# nxtcam_5.net
KiCad netlist of a schematic drawn in EAGLE
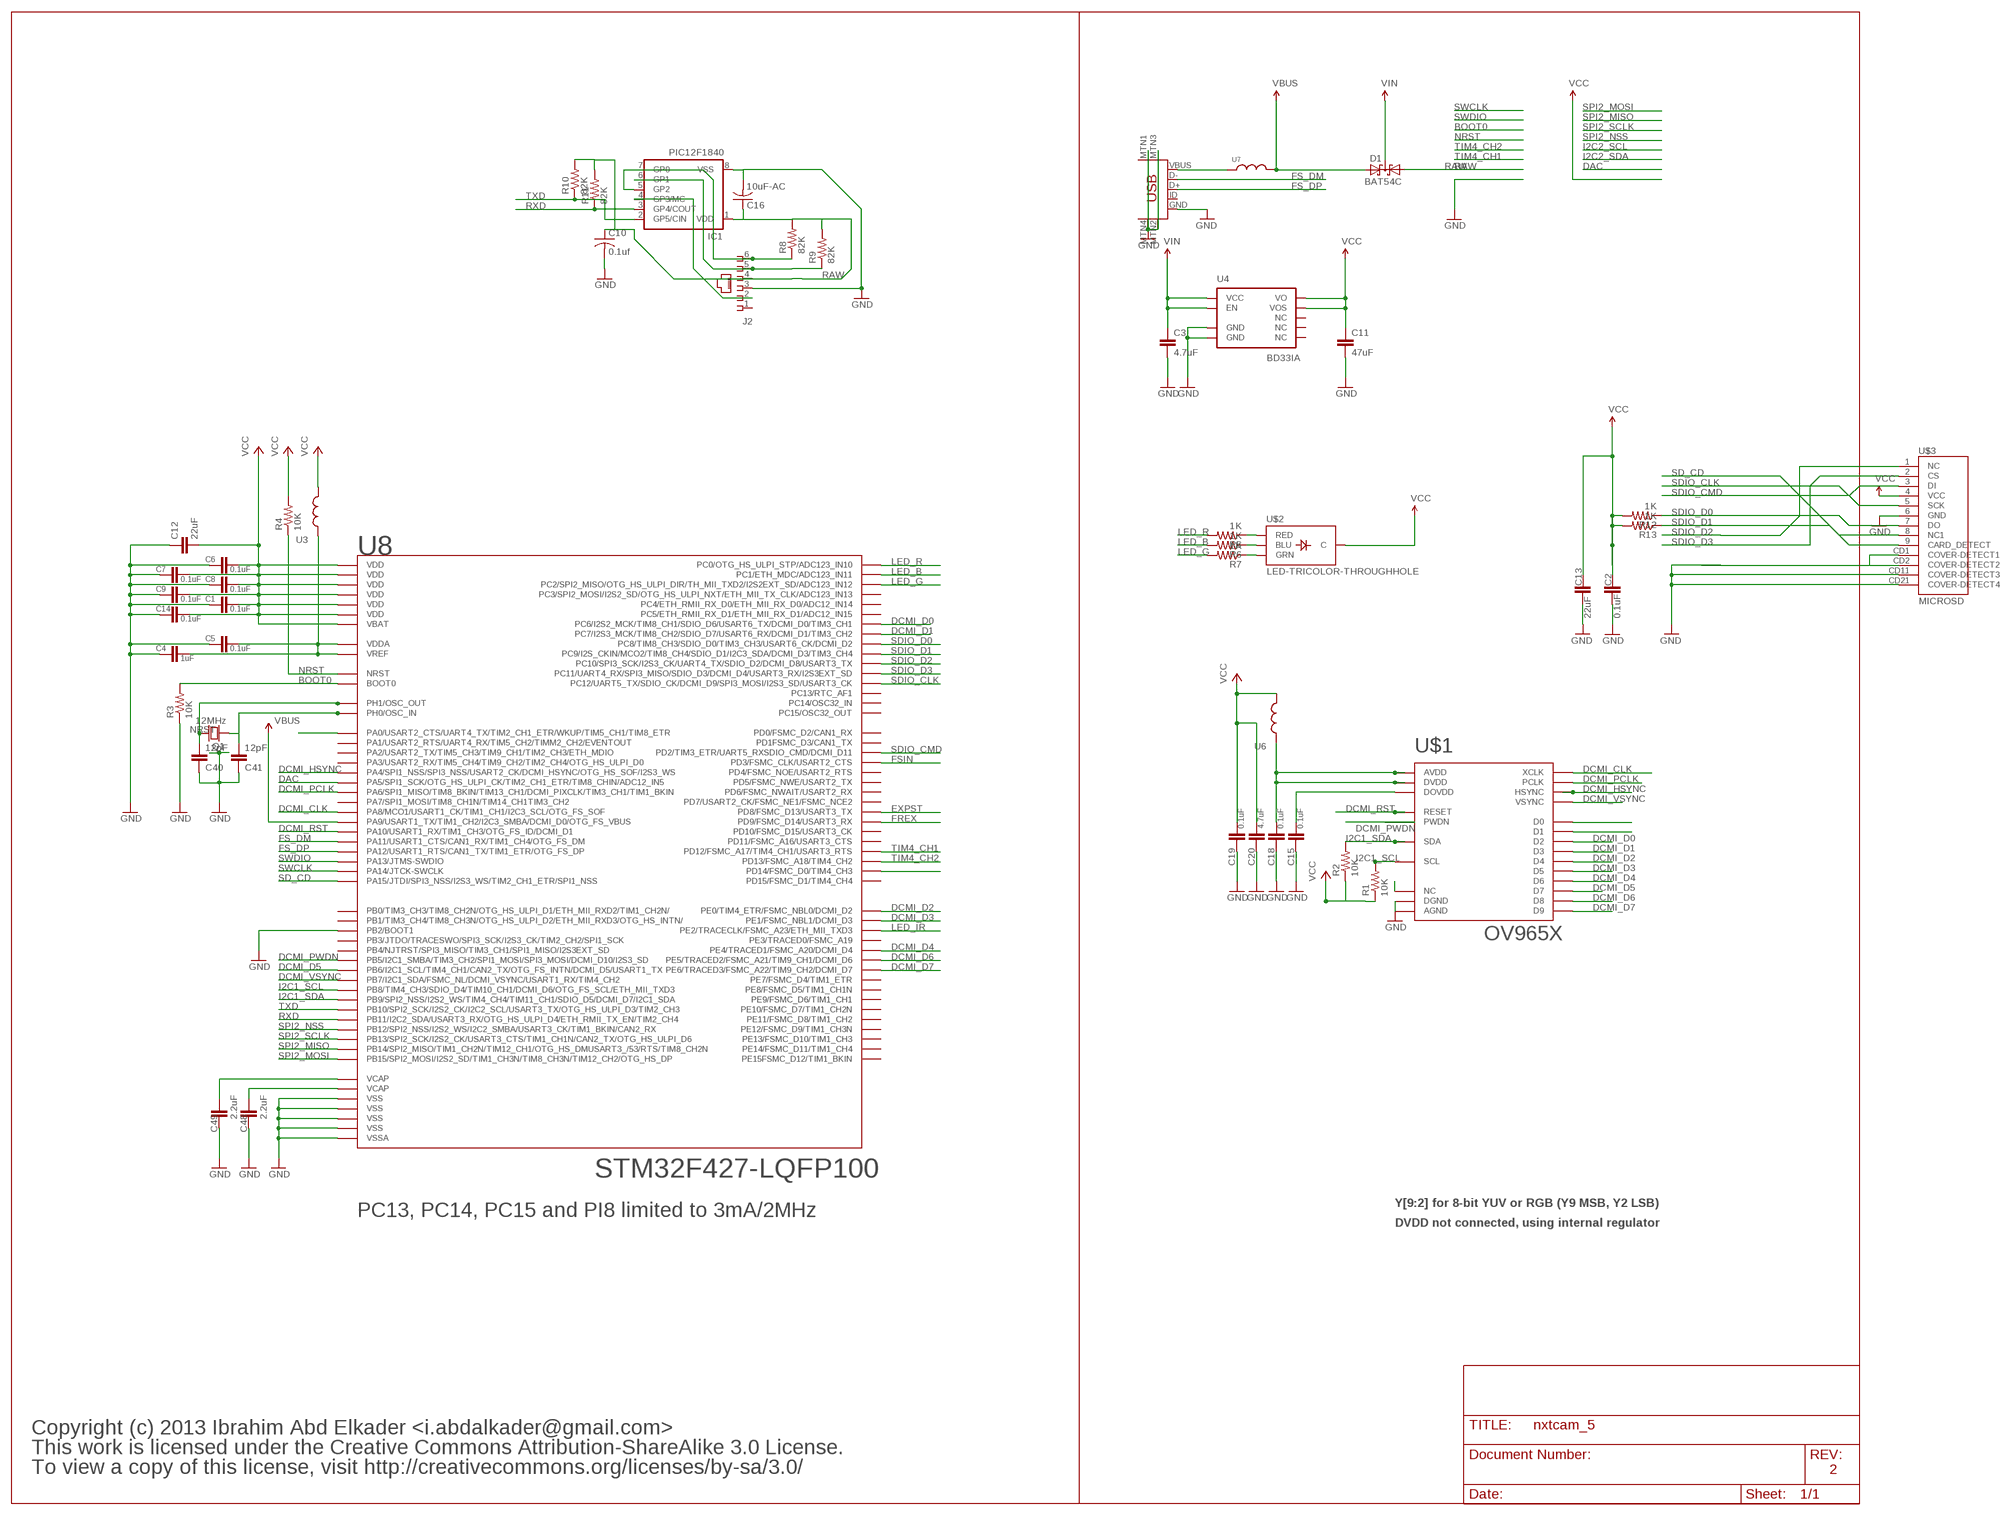
[diagram p0: schematic, sheet 1]

(export (version "E")
  (design (tool "Eeschema 10.0.6"))
  (components
    (comp (ref "C1")
      (value "0.1uF")
      (footprint "eagle-import:0603-CAP")
      (libsource (lib "eagle-import") (part "CAP0603-CAP"))
    )
    (comp (ref "C2")
      (value "0.1uF")
      (footprint "eagle-import:0603-CAP")
      (libsource (lib "eagle-import") (part "CAP0603-CAP"))
    )
    (comp (ref "C3")
      (value "4.7uF")
      (footprint "eagle-import:0603-CAP")
      (libsource (lib "eagle-import") (part "CAP0603-CAP"))
    )
    (comp (ref "C4")
      (value "1uF")
      (footprint "eagle-import:0603-CAP")
      (libsource (lib "eagle-import") (part "CAP0603-CAP"))
    )
    (comp (ref "C5")
      (value "0.1uF")
      (footprint "eagle-import:0603-CAP")
      (libsource (lib "eagle-import") (part "CAP0603-CAP"))
    )
    (comp (ref "C6")
      (value "0.1uF")
      (footprint "eagle-import:0603-CAP")
      (libsource (lib "eagle-import") (part "CAP0603-CAP"))
    )
    (comp (ref "C7")
      (value "0.1uF")
      (footprint "eagle-import:0603-CAP")
      (libsource (lib "eagle-import") (part "CAP0603-CAP"))
    )
    (comp (ref "C8")
      (value "0.1uF")
      (footprint "eagle-import:0603-CAP")
      (libsource (lib "eagle-import") (part "CAP0603-CAP"))
    )
    (comp (ref "C9")
      (value "0.1uF")
      (footprint "eagle-import:0603-CAP")
      (libsource (lib "eagle-import") (part "CAP0603-CAP"))
    )
    (comp (ref "C10")
      (value "0.1uf")
      (footprint "eagle-import:C0603K")
      (libsource (lib "eagle-import") (part "wbyb_C-USC0603K"))
    )
    (comp (ref "C11")
      (value "47uF")
      (footprint "eagle-import:1206")
      (libsource (lib "eagle-import") (part "CAP1206"))
    )
    (comp (ref "C12")
      (value "22uF")
      (footprint "eagle-import:0805")
      (libsource (lib "eagle-import") (part "CAP0805"))
    )
    (comp (ref "C13")
      (value "22uF")
      (footprint "eagle-import:0805")
      (libsource (lib "eagle-import") (part "CAP0805"))
    )
    (comp (ref "C14")
      (value "0.1uF")
      (footprint "eagle-import:0603-CAP")
      (libsource (lib "eagle-import") (part "CAP0603-CAP"))
    )
    (comp (ref "C15")
      (value "0.1uF")
      (footprint "eagle-import:0603-CAP")
      (libsource (lib "eagle-import") (part "CAP0603-CAP"))
    )
    (comp (ref "C16")
      (value "10uF-AC")
      (footprint "eagle-import:C1206K")
      (libsource (lib "eagle-import") (part "C-USC1206K"))
    )
    (comp (ref "C18")
      (value "0.1uF")
      (footprint "eagle-import:0603-CAP")
      (libsource (lib "eagle-import") (part "CAP0603-CAP"))
    )
    (comp (ref "C19")
      (value "0.1uF")
      (footprint "eagle-import:0603-CAP")
      (libsource (lib "eagle-import") (part "CAP0603-CAP"))
    )
    (comp (ref "C20")
      (value "4.7uF")
      (footprint "eagle-import:0603-CAP")
      (libsource (lib "eagle-import") (part "CAP0603-CAP"))
    )
    (comp (ref "C40")
      (value "12pF")
      (footprint "eagle-import:0603-CAP")
      (libsource (lib "eagle-import") (part "CAP0603-CAP"))
    )
    (comp (ref "C41")
      (value "12pF")
      (footprint "eagle-import:0603-CAP")
      (libsource (lib "eagle-import") (part "CAP0603-CAP"))
    )
    (comp (ref "C48")
      (value "2.2uF")
      (footprint "eagle-import:0603-CAP")
      (libsource (lib "eagle-import") (part "CAP0603-CAP"))
    )
    (comp (ref "C49")
      (value "2.2uF")
      (footprint "eagle-import:0603-CAP")
      (libsource (lib "eagle-import") (part "CAP0603-CAP"))
    )
    (comp (ref "D1")
      (value "BAT54C")
      (footprint "eagle-import:SOT23")
      (libsource (lib "eagle-import") (part "BAT54C"))
    )
    (comp (ref "IC1")
      (value "PIC12F1840")
      (footprint "eagle-import:SOIC08")
      (libsource (lib "eagle-import") (part "PIC12F1840"))
    )
    (comp (ref "J2")
      (value "NXTCONN0")
      (footprint "eagle-import:NXTCONN0")
      (libsource (lib "eagle-import") (part "NXTCONN0"))
    )
    (comp (ref "Q1")
      (value "12MHz")
      (footprint "eagle-import:TXC-SMD-50X32")
      (libsource (lib "eagle-import") (part "TXC-CRYSTAL50X32"))
    )
    (comp (ref "R1")
      (value "10K")
      (footprint "eagle-import:0603-RES")
      (libsource (lib "eagle-import") (part "RESISTOR0603-RES"))
    )
    (comp (ref "R2")
      (value "10K")
      (footprint "eagle-import:0603-RES")
      (libsource (lib "eagle-import") (part "RESISTOR0603-RES"))
    )
    (comp (ref "R3")
      (value "10K")
      (footprint "eagle-import:0603-RES")
      (libsource (lib "eagle-import") (part "RESISTOR0603-RES"))
    )
    (comp (ref "R4")
      (value "10K")
      (footprint "eagle-import:0603-RES")
      (libsource (lib "eagle-import") (part "RESISTOR0603-RES"))
    )
    (comp (ref "R5")
      (value "1K")
      (footprint "eagle-import:0603-RES")
      (libsource (lib "eagle-import") (part "RESISTOR0603-RES"))
    )
    (comp (ref "R6")
      (value "1K")
      (footprint "eagle-import:0603-RES")
      (libsource (lib "eagle-import") (part "RESISTOR0603-RES"))
    )
    (comp (ref "R7")
      (value "1K")
      (footprint "eagle-import:0603-RES")
      (libsource (lib "eagle-import") (part "RESISTOR0603-RES"))
    )
    (comp (ref "R8")
      (value "82K")
      (footprint "eagle-import:R0603")
      (libsource (lib "eagle-import") (part "R-US_R0603"))
    )
    (comp (ref "R9")
      (value "82K")
      (footprint "eagle-import:R0603")
      (libsource (lib "eagle-import") (part "R-US_R0603"))
    )
    (comp (ref "R10")
      (value "82K")
      (footprint "eagle-import:R0603")
      (libsource (lib "eagle-import") (part "R-US_R0603"))
    )
    (comp (ref "R11")
      (value "82K")
      (footprint "eagle-import:R0603")
      (libsource (lib "eagle-import") (part "R-US_R0603"))
    )
    (comp (ref "R12")
      (value "1K")
      (footprint "eagle-import:0603-RES")
      (libsource (lib "eagle-import") (part "RESISTOR0603-RES"))
    )
    (comp (ref "R13")
      (value "1K")
      (footprint "eagle-import:0603-RES")
      (libsource (lib "eagle-import") (part "RESISTOR0603-RES"))
    )
    (comp (ref "U$1")
      (value "OV965X")
      (footprint "eagle-import:OV965X")
      (libsource (lib "eagle-import") (part "OV965X"))
    )
    (comp (ref "U$2")
      (value "LED-TRICOLOR-THROUGHHOLE")
      (footprint "eagle-import:LED_TRICOLOR_THROUGHHOLE_SM")
      (libsource (lib "eagle-import") (part "LED-TRICOLOR-THROUGHHOLE"))
    )
    (comp (ref "U$3")
      (value "MICROSD")
      (footprint "eagle-import:MICROSD_CN")
      (libsource (lib "eagle-import") (part "MICROSD"))
    )
    (comp (ref "U$4")
      (value "USB-MINIBTH")
      (footprint "eagle-import:USB-MINIB-ALIGNPINS")
      (libsource (lib "eagle-import") (part "USB-MINIBTH"))
    )
    (comp (ref "U3")
      (value "INDUCTOR0603")
      (footprint "eagle-import:0603")
      (libsource (lib "eagle-import") (part "INDUCTOR0603"))
    )
    (comp (ref "U4")
      (value "BD33IA")
      (footprint "eagle-import:HTSOP-J8")
      (libsource (lib "eagle-import") (part "BD33IA"))
    )
    (comp (ref "U6")
      (value "INDUCTOR0603")
      (footprint "eagle-import:0603")
      (libsource (lib "eagle-import") (part "INDUCTOR0603"))
    )
    (comp (ref "U7")
      (value "INDUCTOR0603")
      (footprint "eagle-import:0603")
      (libsource (lib "eagle-import") (part "INDUCTOR0603"))
    )
    (comp (ref "U8")
      (value "STM32F427-LQFP100")
      (footprint "eagle-import:LQFP100")
      (libsource (lib "eagle-import") (part "STM32F407LQFP100"))
    )
  )
  (nets
    (net (code "1") (name "/BOOT0") (class "Default")
      (node (ref "R3") (pin "2") (pinfunction "2_2") (pintype "passive"))
      (node (ref "U8") (pin "94") (pinfunction "BOOT0_94") (pintype "bidirectional"))
    )
    (net (code "2") (name "/DAC") (class "Default")
      (node (ref "U8") (pin "30") (pinfunction "PA5/SPI1_SCK/OTG_HS_ULPI_CK/TIM2_CH1_ETR/TIM8_CHIN/ADC12_IN5_30") (pintype "bidirectional"))
    )
    (net (code "3") (name "/DCMI_CLK") (class "Default")
      (node (ref "U$1") (pin "P$13") (pinfunction "XCLK_P$13") (pintype "bidirectional"))
      (node (ref "U8") (pin "67") (pinfunction "PA8/MCO1/USART1_CK/TIM1_CH1/I2C3_SCL/OTG_FS_SOF_67") (pintype "bidirectional"))
    )
    (net (code "4") (name "/DCMI_D0") (class "Default")
      (node (ref "U$1") (pin "P$19") (pinfunction "D2_P$19") (pintype "bidirectional"))
      (node (ref "U8") (pin "63") (pinfunction "PC6/I2S2_MCK/TIM8_CH1/SDIO_D6/USART6_TX/DCMI_D0/TIM3_CH1_63") (pintype "bidirectional"))
    )
    (net (code "5") (name "/DCMI_D1") (class "Default")
      (node (ref "U$1") (pin "P$21") (pinfunction "D3_P$21") (pintype "bidirectional"))
      (node (ref "U8") (pin "64") (pinfunction "PC7/I2S3_MCK/TIM8_CH2/SDIO_D7/USART6_RX/DCMI_D1/TIM3_CH2_64") (pintype "bidirectional"))
    )
    (net (code "6") (name "/DCMI_D2") (class "Default")
      (node (ref "U$1") (pin "P$22") (pinfunction "D4_P$22") (pintype "bidirectional"))
      (node (ref "U8") (pin "97") (pinfunction "PE0/TIM4_ETR/FSMC_NBL0/DCMI_D2_97") (pintype "bidirectional"))
    )
    (net (code "7") (name "/DCMI_D3") (class "Default")
      (node (ref "U$1") (pin "P$20") (pinfunction "D5_P$20") (pintype "bidirectional"))
      (node (ref "U8") (pin "98") (pinfunction "PE1/FSMC_NBL1/DCMI_D3_98") (pintype "bidirectional"))
    )
    (net (code "8") (name "/DCMI_D4") (class "Default")
      (node (ref "U$1") (pin "P$18") (pinfunction "D6_P$18") (pintype "bidirectional"))
      (node (ref "U8") (pin "3") (pinfunction "PE4/TRACED1/FSMC_A20/DCMI_D4_3") (pintype "bidirectional"))
    )
    (net (code "9") (name "/DCMI_D5") (class "Default")
      (node (ref "U$1") (pin "P$16") (pinfunction "D7_P$16") (pintype "bidirectional"))
      (node (ref "U8") (pin "92") (pinfunction "PB6/I2C1_SCL/TIM4_CH1/CAN2_TX/OTG_FS_INTN/DCMI_D5/USART1_TX_92") (pintype "bidirectional"))
    )
    (net (code "10") (name "/DCMI_D6") (class "Default")
      (node (ref "U$1") (pin "P$14") (pinfunction "D8_P$14") (pintype "bidirectional"))
      (node (ref "U8") (pin "4") (pinfunction "PE5/TRACED2/FSMC_A21/TIM9_CH1/DCMI_D6_4") (pintype "bidirectional"))
    )
    (net (code "11") (name "/DCMI_D7") (class "Default")
      (node (ref "U$1") (pin "P$12") (pinfunction "D9_P$12") (pintype "bidirectional"))
      (node (ref "U8") (pin "5") (pinfunction "PE6/TRACED3/FSMC_A22/TIM9_CH2/DCMI_D7_5") (pintype "bidirectional"))
    )
    (net (code "12") (name "/DCMI_HSYNC") (class "Default")
      (node (ref "U$1") (pin "P$9") (pinfunction "HSYNC_P$9") (pintype "bidirectional"))
      (node (ref "U8") (pin "29") (pinfunction "PA4/SPI1_NSS/SPI3_NSS/USART2_CK/DCMI_HSYNC/OTG_HS_SOF/I2S3_WS_29") (pintype "bidirectional"))
    )
    (net (code "13") (name "/DCMI_PCLK") (class "Default")
      (node (ref "U$1") (pin "P$17") (pinfunction "PCLK_P$17") (pintype "bidirectional"))
      (node (ref "U8") (pin "31") (pinfunction "PA6/SPI1_MISO/TIM8_BKIN/TIM13_CH1/DCMI_PIXCLK/TIM3_CH1/TIM1_BKIN_31") (pintype "bidirectional"))
    )
    (net (code "14") (name "/DCMI_PWDN") (class "Default")
      (node (ref "U$1") (pin "P$8") (pinfunction "PWDN_P$8") (pintype "bidirectional"))
      (node (ref "U8") (pin "91") (pinfunction "PB5/I2C1_SMBA/TIM3_CH2/SPI1_MOSI/SPI3_MOSI/DCMI_D10/I2S3_SD_91") (pintype "bidirectional"))
    )
    (net (code "15") (name "/DCMI_RST") (class "Default")
      (node (ref "U$1") (pin "P$6") (pinfunction "RESET_P$6") (pintype "bidirectional"))
      (node (ref "U8") (pin "69") (pinfunction "PA10/USART1_RX/TIM1_CH3/OTG_FS_ID/DCMI_D1_69") (pintype "bidirectional"))
    )
    (net (code "16") (name "/DCMI_VSYNC") (class "Default")
      (node (ref "U$1") (pin "P$7") (pinfunction "VSYNC_P$7") (pintype "bidirectional"))
      (node (ref "U8") (pin "93") (pinfunction "PB7/I2C1_SDA/FSMC_NL/DCMI_VSYNC/USART1_RX/TIM4_CH2_93") (pintype "bidirectional"))
    )
    (net (code "17") (name "/EXPST") (class "Default")
      (node (ref "U8") (pin "55") (pinfunction "PD8/FSMC_D13/USART3_TX_55") (pintype "bidirectional"))
    )
    (net (code "18") (name "/FREX") (class "Default")
      (node (ref "U8") (pin "56") (pinfunction "PD9/FSMC_D14/USART3_RX_56") (pintype "bidirectional"))
    )
    (net (code "19") (name "/FSIN") (class "Default")
      (node (ref "U8") (pin "84") (pinfunction "PD3/FSMC_CLK/USART2_CTS_84") (pintype "bidirectional"))
    )
    (net (code "20") (name "/FS_DM") (class "Default")
      (node (ref "U$4") (pin "D-") (pinfunction "D-_D-") (pintype "bidirectional"))
      (node (ref "U8") (pin "70") (pinfunction "PA11/USART1_CTS/CAN1_RX/TIM1_CH4/OTG_FS_DM_70") (pintype "bidirectional"))
    )
    (net (code "21") (name "/FS_DP") (class "Default")
      (node (ref "U$4") (pin "D+") (pinfunction "D+_D+") (pintype "bidirectional"))
      (node (ref "U8") (pin "71") (pinfunction "PA12/USART1_RTS/CAN1_TX/TIM1_ETR/OTG_FS_DP_71") (pintype "bidirectional"))
    )
    (net (code "22") (name "/I2C1_SCL") (class "Default")
      (node (ref "R1") (pin "2") (pinfunction "2_2") (pintype "passive"))
      (node (ref "U$1") (pin "P$5") (pinfunction "SCL_P$5") (pintype "bidirectional"))
      (node (ref "U8") (pin "95") (pinfunction "PB8/TIM4_CH3/SDIO_D4/TIM10_CH1/DCMI_D6/OTG_FS_SCL/ETH_MII_TXD3_95") (pintype "bidirectional"))
    )
    (net (code "23") (name "/I2C1_SDA") (class "Default")
      (node (ref "R2") (pin "2") (pinfunction "2_2") (pintype "passive"))
      (node (ref "U$1") (pin "P$3") (pinfunction "SDA_P$3") (pintype "bidirectional"))
      (node (ref "U8") (pin "96") (pinfunction "PB9/SPI2_NSS/I2S2_WS/TIM4_CH4/TIM11_CH1/SDIO_D5/DCMI_D7/I2C1_SDA_96") (pintype "bidirectional"))
    )
    (net (code "26") (name "/LED_B") (class "Default")
      (node (ref "R6") (pin "2") (pinfunction "2_2") (pintype "passive"))
      (node (ref "U8") (pin "16") (pinfunction "PC1/ETH_MDC/ADC123_IN11_16") (pintype "bidirectional"))
    )
    (net (code "27") (name "/LED_G") (class "Default")
      (node (ref "R7") (pin "2") (pinfunction "2_2") (pintype "passive"))
      (node (ref "U8") (pin "17") (pinfunction "PC2/SPI2_MISO/OTG_HS_ULPI_DIR/TH_MII_TXD2/I2S2EXT_SD/ADC123_IN12_17") (pintype "bidirectional"))
    )
    (net (code "28") (name "/LED_IR") (class "Default")
      (node (ref "U8") (pin "1") (pinfunction "PE2/TRACECLK/FSMC_A23/ETH_MII_TXD3_1") (pintype "bidirectional"))
    )
    (net (code "29") (name "/LED_R") (class "Default")
      (node (ref "R5") (pin "2") (pinfunction "2_2") (pintype "passive"))
      (node (ref "U8") (pin "15") (pinfunction "PC0/OTG_HS_ULPI_STP/ADC123_IN10_15") (pintype "bidirectional"))
    )
    (net (code "30") (name "/NRST") (class "Default")
      (node (ref "R4") (pin "1") (pinfunction "1_1") (pintype "passive"))
      (node (ref "U8") (pin "14") (pinfunction "NRST_14") (pintype "bidirectional"))
    )
    (net (code "31") (name "/RAW") (class "Default")
      (node (ref "C10") (pin "1") (pinfunction "1_1") (pintype "passive"))
      (node (ref "C16") (pin "1") (pinfunction "1_1") (pintype "passive"))
      (node (ref "D1") (pin "1") (pinfunction "A1_1") (pintype "passive"))
      (node (ref "IC1") (pin "1") (pinfunction "VDD_1") (pintype "power_in"))
      (node (ref "J2") (pin "4") (pinfunction "4_4") (pintype "passive"))
      (node (ref "R10") (pin "2") (pinfunction "2_2") (pintype "passive"))
      (node (ref "R11") (pin "2") (pinfunction "2_2") (pintype "passive"))
      (node (ref "R8") (pin "2") (pinfunction "2_2") (pintype "passive"))
      (node (ref "R9") (pin "2") (pinfunction "2_2") (pintype "passive"))
    )
    (net (code "32") (name "/RXD") (class "Default")
      (node (ref "IC1") (pin "3") (pinfunction "GP4/COUT_3") (pintype "bidirectional"))
      (node (ref "R11") (pin "1") (pinfunction "1_1") (pintype "passive"))
      (node (ref "U8") (pin "48") (pinfunction "PB11/I2C2_SDA/USART3_RX/OTG_HS_ULPI_D4/ETH_RMII_TX_EN/TIM2_CH4_48") (pintype "bidirectional"))
    )
    (net (code "33") (name "/SDIO_CLK") (class "Default")
      (node (ref "U$3") (pin "5") (pinfunction "SCK_5") (pintype "bidirectional"))
      (node (ref "U8") (pin "80") (pinfunction "PC12/UART5_TX/SDIO_CK/DCMI_D9/SPI3_MOSI/I2S3_SD/USART3_CK_80") (pintype "bidirectional"))
    )
    (net (code "34") (name "/SDIO_CMD") (class "Default")
      (node (ref "U$3") (pin "3") (pinfunction "DI_3") (pintype "bidirectional"))
      (node (ref "U8") (pin "83") (pinfunction "PD2/TIM3_ETR/UART5_RXSDIO_CMD/DCMI_D11_83") (pintype "bidirectional"))
    )
    (net (code "35") (name "/SDIO_D0") (class "Default")
      (node (ref "R12") (pin "1") (pinfunction "1_1") (pintype "passive"))
      (node (ref "U$3") (pin "7") (pinfunction "DO_7") (pintype "bidirectional"))
      (node (ref "U8") (pin "65") (pinfunction "PC8/TIM8_CH3/SDIO_D0/TIM3_CH3/USART6_CK/DCMI_D2_65") (pintype "bidirectional"))
    )
    (net (code "36") (name "/SDIO_D1") (class "Default")
      (node (ref "R13") (pin "1") (pinfunction "1_1") (pintype "passive"))
      (node (ref "U$3") (pin "8") (pinfunction "NC1_8") (pintype "bidirectional"))
      (node (ref "U8") (pin "66") (pinfunction "PC9/I2S_CKIN/MCO2/TIM8_CH4/SDIO_D1/I2C3_SDA/DCMI_D3/TIM3_CH4_66") (pintype "bidirectional"))
    )
    (net (code "37") (name "/SDIO_D2") (class "Default")
      (node (ref "U$3") (pin "1") (pinfunction "NC_1") (pintype "bidirectional"))
      (node (ref "U8") (pin "78") (pinfunction "PC10/SPI3_SCK/I2S3_CK/UART4_TX/SDIO_D2/DCMI_D8/USART3_TX_78") (pintype "bidirectional"))
    )
    (net (code "38") (name "/SDIO_D3") (class "Default")
      (node (ref "U$3") (pin "2") (pinfunction "CS_2") (pintype "bidirectional"))
      (node (ref "U8") (pin "79") (pinfunction "PC11/UART4_RX/SPI3_MISO/SDIO_D3/DCMI_D4/USART3_RX/I2S3EXT_SD_79") (pintype "bidirectional"))
    )
    (net (code "39") (name "/SD_CD") (class "Default")
      (node (ref "U$3") (pin "9") (pinfunction "CARD_DETECT_9") (pintype "bidirectional"))
      (node (ref "U8") (pin "77") (pinfunction "PA15/JTDI/SPI3_NSS/I2S3_WS/TIM2_CH1_ETR/SPI1_NSS_77") (pintype "bidirectional"))
    )
    (net (code "40") (name "/SPI2_MISO") (class "Default")
      (node (ref "U8") (pin "53") (pinfunction "PB14/SPI2_MISO/TIM1_CH2N/TIM12_CH1/OTG_HS_DMUSART3_/53/RTS/TIM8_CH2N_53") (pintype "bidirectional"))
    )
    (net (code "41") (name "/SPI2_MOSI") (class "Default")
      (node (ref "U8") (pin "54") (pinfunction "PB15/SPI2_MOSI/I2S2_SD/TIM1_CH3N/TIM8_CH3N/TIM12_CH2/OTG_HS_DP_54") (pintype "bidirectional"))
    )
    (net (code "42") (name "/SPI2_NSS") (class "Default")
      (node (ref "U8") (pin "51") (pinfunction "PB12/SPI2_NSS/I2S2_WS/I2C2_SMBA/USART3_CK/TIM1_BKIN/CAN2_RX_51") (pintype "bidirectional"))
    )
    (net (code "43") (name "/SPI2_SCLK") (class "Default")
      (node (ref "U8") (pin "52") (pinfunction "PB13/SPI2_SCK/I2S2_CK/USART3_CTS/TIM1_CH1N/CAN2_TX/OTG_HS_ULPI_D6_52") (pintype "bidirectional"))
    )
    (net (code "44") (name "/SWCLK") (class "Default")
      (node (ref "U8") (pin "76") (pinfunction "PA14/JTCK-SWCLK_76") (pintype "bidirectional"))
    )
    (net (code "45") (name "/SWDIO") (class "Default")
      (node (ref "U8") (pin "72") (pinfunction "PA13/JTMS-SWDIO_72") (pintype "bidirectional"))
    )
    (net (code "46") (name "/TIM4_CH1") (class "Default")
      (node (ref "U8") (pin "59") (pinfunction "PD12/FSMC_A17/TIM4_CH1/USART3_RTS_59") (pintype "bidirectional"))
    )
    (net (code "47") (name "/TIM4_CH2") (class "Default")
      (node (ref "U8") (pin "60") (pinfunction "PD13/FSMC_A18/TIM4_CH2_60") (pintype "bidirectional"))
    )
    (net (code "48") (name "/TXD") (class "Default")
      (node (ref "IC1") (pin "2") (pinfunction "GP5/CIN_2") (pintype "bidirectional"))
      (node (ref "R10") (pin "1") (pinfunction "1_1") (pintype "passive"))
      (node (ref "U8") (pin "47") (pinfunction "PB10/SPI2_SCK/I2S2_CK/I2C2_SCL/USART3_TX/OTG_HS_ULPI_D3/TIM2_CH3_47") (pintype "bidirectional"))
    )
    (net (code "49") (name "GND") (class "Default")
      (node (ref "C1") (pin "2") (pinfunction "2_2") (pintype "passive"))
      (node (ref "C10") (pin "2") (pinfunction "2_2") (pintype "passive"))
      (node (ref "C11") (pin "2") (pinfunction "2_2") (pintype "passive"))
      (node (ref "C12") (pin "1") (pinfunction "1_1") (pintype "passive"))
      (node (ref "C13") (pin "2") (pinfunction "2_2") (pintype "passive"))
      (node (ref "C14") (pin "2") (pinfunction "2_2") (pintype "passive"))
      (node (ref "C15") (pin "2") (pinfunction "2_2") (pintype "passive"))
      (node (ref "C16") (pin "2") (pinfunction "2_2") (pintype "passive"))
      (node (ref "C18") (pin "2") (pinfunction "2_2") (pintype "passive"))
      (node (ref "C19") (pin "2") (pinfunction "2_2") (pintype "passive"))
      (node (ref "C2") (pin "2") (pinfunction "2_2") (pintype "passive"))
      (node (ref "C20") (pin "2") (pinfunction "2_2") (pintype "passive"))
      (node (ref "C3") (pin "2") (pinfunction "2_2") (pintype "passive"))
      (node (ref "C4") (pin "2") (pinfunction "2_2") (pintype "passive"))
      (node (ref "C40") (pin "1") (pinfunction "1_1") (pintype "passive"))
      (node (ref "C41") (pin "1") (pinfunction "1_1") (pintype "passive"))
      (node (ref "C48") (pin "2") (pinfunction "2_2") (pintype "passive"))
      (node (ref "C49") (pin "2") (pinfunction "2_2") (pintype "passive"))
      (node (ref "C5") (pin "2") (pinfunction "2_2") (pintype "passive"))
      (node (ref "C6") (pin "2") (pinfunction "2_2") (pintype "passive"))
      (node (ref "C7") (pin "2") (pinfunction "2_2") (pintype "passive"))
      (node (ref "C8") (pin "2") (pinfunction "2_2") (pintype "passive"))
      (node (ref "C9") (pin "2") (pinfunction "2_2") (pintype "passive"))
      (node (ref "IC1") (pin "8") (pinfunction "VSS_8") (pintype "power_in"))
      (node (ref "J2") (pin "3") (pinfunction "3_3") (pintype "passive"))
      (node (ref "R3") (pin "1") (pinfunction "1_1") (pintype "passive"))
      (node (ref "U$1") (pin "P$15") (pinfunction "DGND_P$15") (pintype "bidirectional"))
      (node (ref "U$1") (pin "P$2") (pinfunction "AGND_P$2") (pintype "power_in"))
      (node (ref "U$3") (pin "6") (pinfunction "GND_6") (pintype "bidirectional"))
      (node (ref "U$3") (pin "CD1") (pinfunction "COVER-DETECT1_CD1") (pintype "bidirectional"))
      (node (ref "U$3") (pin "CD11") (pinfunction "COVER-DETECT3_CD11") (pintype "bidirectional"))
      (node (ref "U$3") (pin "CD2") (pinfunction "COVER-DETECT2_CD2") (pintype "bidirectional"))
      (node (ref "U$3") (pin "CD21") (pinfunction "COVER-DETECT4_CD21") (pintype "bidirectional"))
      (node (ref "U$4") (pin "GND") (pinfunction "GND_GND") (pintype "bidirectional"))
      (node (ref "U$4") (pin "MTN1") (pinfunction "MTN2_MTN1") (pintype "bidirectional"))
      (node (ref "U$4") (pin "MTN2") (pinfunction "MTN3_MTN2") (pintype "bidirectional"))
      (node (ref "U$4") (pin "MTN3") (pinfunction "MTN1_MTN3") (pintype "bidirectional"))
      (node (ref "U$4") (pin "MTN4") (pinfunction "MTN4_MTN4") (pintype "bidirectional"))
      (node (ref "U4") (pin "3") (pinfunction "GND_3") (pintype "input"))
      (node (ref "U4") (pin "P$1") (pinfunction "GND_P$1") (pintype "input"))
      (node (ref "U8") (pin "10") (pinfunction "VSS_10") (pintype "power_in"))
      (node (ref "U8") (pin "20") (pinfunction "VSSA_20") (pintype "power_in"))
      (node (ref "U8") (pin "27") (pinfunction "VSS_27") (pintype "power_in"))
      (node (ref "U8") (pin "37") (pinfunction "PB2/BOOT1_37") (pintype "bidirectional"))
      (node (ref "U8") (pin "74") (pinfunction "VSS_74") (pintype "power_in"))
      (node (ref "U8") (pin "99") (pinfunction "VSS_99") (pintype "power_in"))
    )
    (net (code "50") (name "Net-(C48-Pad1)") (class "Default")
      (node (ref "C48") (pin "1") (pinfunction "1_1") (pintype "passive"))
      (node (ref "U8") (pin "73") (pinfunction "VCAP_73") (pintype "power_in"))
    )
    (net (code "51") (name "Net-(C49-Pad1)") (class "Default")
      (node (ref "C49") (pin "1") (pinfunction "1_1") (pintype "passive"))
      (node (ref "U8") (pin "49") (pinfunction "VCAP_49") (pintype "power_in"))
    )
    (net (code "52") (name "Net-(IC1-GP0)") (class "Default")
      (node (ref "IC1") (pin "5") (pinfunction "GP2_5") (pintype "bidirectional"))
      (node (ref "IC1") (pin "7") (pinfunction "GP0_7") (pintype "bidirectional"))
      (node (ref "J2") (pin "6") (pinfunction "6_6") (pintype "passive"))
      (node (ref "R8") (pin "1") (pinfunction "1_1") (pintype "passive"))
    )
    (net (code "53") (name "Net-(IC1-GP1)") (class "Default")
      (node (ref "IC1") (pin "6") (pinfunction "GP1_6") (pintype "bidirectional"))
      (node (ref "J2") (pin "5") (pinfunction "5_5") (pintype "passive"))
      (node (ref "R9") (pin "1") (pinfunction "1_1") (pintype "passive"))
    )
    (net (code "54") (name "Net-(IC1-GP3{slash}MC)") (class "Default")
      (node (ref "IC1") (pin "4") (pinfunction "GP3/MC_4") (pintype "input"))
      (node (ref "J2") (pin "2") (pinfunction "2_2") (pintype "passive"))
    )
    (net (code "55") (name "Net-(R5-Pad1)") (class "Default")
      (node (ref "R5") (pin "1") (pinfunction "1_1") (pintype "passive"))
      (node (ref "U$2") (pin "RED") (pinfunction "RED_RED") (pintype "bidirectional"))
    )
    (net (code "56") (name "Net-(R6-Pad1)") (class "Default")
      (node (ref "R6") (pin "1") (pinfunction "1_1") (pintype "passive"))
      (node (ref "U$2") (pin "BLU") (pinfunction "BLU_BLU") (pintype "bidirectional"))
    )
    (net (code "57") (name "Net-(R7-Pad1)") (class "Default")
      (node (ref "R7") (pin "1") (pinfunction "1_1") (pintype "passive"))
      (node (ref "U$2") (pin "GRN") (pinfunction "GRN_GRN") (pintype "bidirectional"))
    )
    (net (code "58") (name "Net-(U$1-AVDD)") (class "Default")
      (node (ref "C18") (pin "1") (pinfunction "1_1") (pintype "passive"))
      (node (ref "U$1") (pin "P$10") (pinfunction "DVDD_P$10") (pintype "bidirectional"))
      (node (ref "U$1") (pin "P$4") (pinfunction "AVDD_P$4") (pintype "power_in"))
      (node (ref "U6") (pin "1") (pinfunction "1_1") (pintype "passive"))
    )
    (net (code "59") (name "Net-(U$1-DOVDD)") (class "Default")
      (node (ref "C15") (pin "1") (pinfunction "1_1") (pintype "passive"))
      (node (ref "U$1") (pin "P$11") (pinfunction "DOVDD_P$11") (pintype "bidirectional"))
    )
    (net (code "60") (name "Net-(U$4-PadVBUS)") (class "Default")
      (node (ref "U$4") (pin "VBUS") (pinfunction "VBUS_VBUS") (pintype "bidirectional"))
      (node (ref "U7") (pin "1") (pinfunction "1_1") (pintype "passive"))
    )
    (net (code "61") (name "Net-(U8-PH0{slash}OSC_IN)") (class "Default")
      (node (ref "C41") (pin "2") (pinfunction "2_2") (pintype "passive"))
      (node (ref "Q1") (pin "P$1") (pinfunction "P$1_P$1") (pintype "passive"))
      (node (ref "U8") (pin "12") (pinfunction "PH0/OSC_IN_12") (pintype "bidirectional"))
    )
    (net (code "62") (name "Net-(U8-PH1{slash}OSC_OUT)") (class "Default")
      (node (ref "C40") (pin "2") (pinfunction "2_2") (pintype "passive"))
      (node (ref "Q1") (pin "P$2") (pinfunction "P$2_P$2") (pintype "passive"))
      (node (ref "U8") (pin "13") (pinfunction "PH1/OSC_OUT_13") (pintype "bidirectional"))
    )
    (net (code "63") (name "Net-(U8-VDDA)") (class "Default")
      (node (ref "C4") (pin "1") (pinfunction "1_1") (pintype "passive"))
      (node (ref "C5") (pin "1") (pinfunction "1_1") (pintype "passive"))
      (node (ref "U3") (pin "1") (pinfunction "1_1") (pintype "passive"))
      (node (ref "U8") (pin "21") (pinfunction "VREF_21") (pintype "power_in"))
      (node (ref "U8") (pin "22") (pinfunction "VDDA_22") (pintype "power_in"))
    )
    (net (code "64") (name "VBUS") (class "Default")
      (node (ref "D1") (pin "2") (pinfunction "A2_2") (pintype "passive"))
      (node (ref "U7") (pin "2") (pinfunction "2_2") (pintype "passive"))
      (node (ref "U8") (pin "68") (pinfunction "PA9/USART1_TX/TIM1_CH2/I2C3_SMBA/DCMI_D0/OTG_FS_VBUS_68") (pintype "bidirectional"))
    )
    (net (code "65") (name "VCC") (class "Default")
      (node (ref "C1") (pin "1") (pinfunction "1_1") (pintype "passive"))
      (node (ref "C11") (pin "1") (pinfunction "1_1") (pintype "passive"))
      (node (ref "C12") (pin "2") (pinfunction "2_2") (pintype "passive"))
      (node (ref "C13") (pin "1") (pinfunction "1_1") (pintype "passive"))
      (node (ref "C14") (pin "1") (pinfunction "1_1") (pintype "passive"))
      (node (ref "C19") (pin "1") (pinfunction "1_1") (pintype "passive"))
      (node (ref "C2") (pin "1") (pinfunction "1_1") (pintype "passive"))
      (node (ref "C20") (pin "1") (pinfunction "1_1") (pintype "passive"))
      (node (ref "C6") (pin "1") (pinfunction "1_1") (pintype "passive"))
      (node (ref "C7") (pin "1") (pinfunction "1_1") (pintype "passive"))
      (node (ref "C8") (pin "1") (pinfunction "1_1") (pintype "passive"))
      (node (ref "C9") (pin "1") (pinfunction "1_1") (pintype "passive"))
      (node (ref "R1") (pin "1") (pinfunction "1_1") (pintype "passive"))
      (node (ref "R12") (pin "2") (pinfunction "2_2") (pintype "passive"))
      (node (ref "R13") (pin "2") (pinfunction "2_2") (pintype "passive"))
      (node (ref "R2") (pin "1") (pinfunction "1_1") (pintype "passive"))
      (node (ref "R4") (pin "2") (pinfunction "2_2") (pintype "passive"))
      (node (ref "U$2") (pin "GND") (pinfunction "C_GND") (pintype "bidirectional"))
      (node (ref "U$3") (pin "4") (pinfunction "VCC_4") (pintype "bidirectional"))
      (node (ref "U3") (pin "2") (pinfunction "2_2") (pintype "passive"))
      (node (ref "U4") (pin "1") (pinfunction "VO_1") (pintype "output"))
      (node (ref "U4") (pin "2") (pinfunction "VOS_2") (pintype "output"))
      (node (ref "U6") (pin "2") (pinfunction "2_2") (pintype "passive"))
      (node (ref "U8") (pin "100") (pinfunction "VDD_100") (pintype "power_in"))
      (node (ref "U8") (pin "11") (pinfunction "VDD_11") (pintype "power_in"))
      (node (ref "U8") (pin "19") (pinfunction "VDD_19") (pintype "power_in"))
      (node (ref "U8") (pin "28") (pinfunction "VDD_28") (pintype "power_in"))
      (node (ref "U8") (pin "50") (pinfunction "VDD_50") (pintype "power_in"))
      (node (ref "U8") (pin "6") (pinfunction "VBAT_6") (pintype "power_in"))
      (node (ref "U8") (pin "75") (pinfunction "VDD_75") (pintype "power_in"))
    )
    (net (code "66") (name "VIN") (class "Default")
      (node (ref "C3") (pin "1") (pinfunction "1_1") (pintype "passive"))
      (node (ref "D1") (pin "3") (pinfunction "CC_3") (pintype "passive"))
      (node (ref "U4") (pin "5") (pinfunction "EN_5") (pintype "input"))
      (node (ref "U4") (pin "8") (pinfunction "VCC_8") (pintype "input"))
    )
    (net (code "67") (name "unconnected-(J2-Pad1)") (class "Default")
      (node (ref "J2") (pin "1") (pinfunction "1_1") (pintype "passive"))
    )
    (net (code "68") (name "unconnected-(U$1-D0-PadP$24)") (class "Default")
      (node (ref "U$1") (pin "P$24") (pinfunction "D0_P$24") (pintype "bidirectional"))
    )
    (net (code "69") (name "unconnected-(U$1-D1-PadP$23)") (class "Default")
      (node (ref "U$1") (pin "P$23") (pinfunction "D1_P$23") (pintype "bidirectional"))
    )
    (net (code "70") (name "unconnected-(U$1-NC-PadP$1)") (class "Default")
      (node (ref "U$1") (pin "P$1") (pinfunction "NC_P$1") (pintype "no_connect"))
    )
    (net (code "71") (name "unconnected-(U$4-PadID)") (class "Default")
      (node (ref "U$4") (pin "ID") (pinfunction "ID_ID") (pintype "bidirectional"))
    )
    (net (code "72") (name "unconnected-(U4-NC-Pad4)") (class "Default")
      (node (ref "U4") (pin "4") (pinfunction "NC_4") (pintype "input"))
    )
    (net (code "73") (name "unconnected-(U4-NC-Pad6)") (class "Default")
      (node (ref "U4") (pin "6") (pinfunction "NC_6") (pintype "bidirectional"))
    )
    (net (code "74") (name "unconnected-(U4-NC-Pad7)") (class "Default")
      (node (ref "U4") (pin "7") (pinfunction "NC_7") (pintype "input"))
    )
    (net (code "75") (name "unconnected-(U8-PA0{slash}USART2_CTS{slash}UART4_TX{slash}TIM2_CH1_ETR{slash}WKUP{slash}TIM5_CH1{slash}TIM8_ETR-Pad23)") (class "Default")
      (node (ref "U8") (pin "23") (pinfunction "PA0/USART2_CTS/UART4_TX/TIM2_CH1_ETR/WKUP/TIM5_CH1/TIM8_ETR_23") (pintype "bidirectional"))
    )
    (net (code "76") (name "unconnected-(U8-PA1{slash}USART2_RTS{slash}UART4_RX{slash}TIM5_CH2{slash}TIMM2_CH2{slash}EVENTOUT-Pad24)") (class "Default")
      (node (ref "U8") (pin "24") (pinfunction "PA1/USART2_RTS/UART4_RX/TIM5_CH2/TIMM2_CH2/EVENTOUT_24") (pintype "bidirectional"))
    )
    (net (code "77") (name "unconnected-(U8-PA2{slash}USART2_TX{slash}TIM5_CH3{slash}TIM9_CH1{slash}TIM2_CH3{slash}ETH_MDIO-Pad25)") (class "Default")
      (node (ref "U8") (pin "25") (pinfunction "PA2/USART2_TX/TIM5_CH3/TIM9_CH1/TIM2_CH3/ETH_MDIO_25") (pintype "bidirectional"))
    )
    (net (code "78") (name "unconnected-(U8-PA3{slash}USART2_RX{slash}TIM5_CH4{slash}TIM9_CH2{slash}TIM2_CH4{slash}OTG_HS_ULPI_D0-Pad26)") (class "Default")
      (node (ref "U8") (pin "26") (pinfunction "PA3/USART2_RX/TIM5_CH4/TIM9_CH2/TIM2_CH4/OTG_HS_ULPI_D0_26") (pintype "bidirectional"))
    )
    (net (code "79") (name "unconnected-(U8-PA7{slash}SPI1_MOSI{slash}TIM8_CH1N{slash}TIM14_CH1TIM3_CH2-Pad32)") (class "Default")
      (node (ref "U8") (pin "32") (pinfunction "PA7/SPI1_MOSI/TIM8_CH1N/TIM14_CH1TIM3_CH2_32") (pintype "bidirectional"))
    )
    (net (code "80") (name "unconnected-(U8-PB0{slash}TIM3_CH3{slash}TIM8_CH2N{slash}OTG_HS_ULPI_D1{slash}ETH_MII_RXD2{slash}TIM1_CH2N{slash}-Pad35)") (class "Default")
      (node (ref "U8") (pin "35") (pinfunction "PB0/TIM3_CH3/TIM8_CH2N/OTG_HS_ULPI_D1/ETH_MII_RXD2/TIM1_CH2N/_35") (pintype "bidirectional"))
    )
    (net (code "81") (name "unconnected-(U8-PB1{slash}TIM3_CH4{slash}TIM8_CH3N{slash}OTG_HS_ULPI_D2{slash}ETH_MII_RXD3{slash}OTG_HS_INTN{slash}-Pad36)") (class "Default")
      (node (ref "U8") (pin "36") (pinfunction "PB1/TIM3_CH4/TIM8_CH3N/OTG_HS_ULPI_D2/ETH_MII_RXD3/OTG_HS_INTN/_36") (pintype "bidirectional"))
    )
    (net (code "82") (name "unconnected-(U8-PB3{slash}JTDO{slash}TRACESWO{slash}SPI3_SCK{slash}I2S3_CK{slash}TIM2_CH2{slash}SPI1_SCK-Pad89)") (class "Default")
      (node (ref "U8") (pin "89") (pinfunction "PB3/JTDO/TRACESWO/SPI3_SCK/I2S3_CK/TIM2_CH2/SPI1_SCK_89") (pintype "bidirectional"))
    )
    (net (code "83") (name "unconnected-(U8-PB4{slash}NJTRST{slash}SPI3_MISO{slash}TIM3_CH1{slash}SPI1_MISO{slash}I2S3EXT_SD-Pad90)") (class "Default")
      (node (ref "U8") (pin "90") (pinfunction "PB4/NJTRST/SPI3_MISO/TIM3_CH1/SPI1_MISO/I2S3EXT_SD_90") (pintype "bidirectional"))
    )
    (net (code "84") (name "unconnected-(U8-PC3{slash}SPI2_MOSI{slash}I2S2_SD{slash}OTG_HS_ULPI_NXT{slash}ETH_MII_TX_CLK{slash}ADC123_IN13-Pad18)") (class "Default")
      (node (ref "U8") (pin "18") (pinfunction "PC3/SPI2_MOSI/I2S2_SD/OTG_HS_ULPI_NXT/ETH_MII_TX_CLK/ADC123_IN13_18") (pintype "bidirectional"))
    )
    (net (code "85") (name "unconnected-(U8-PC4{slash}ETH_RMII_RX_D0{slash}ETH_MII_RX_D0{slash}ADC12_IN14-Pad33)") (class "Default")
      (node (ref "U8") (pin "33") (pinfunction "PC4/ETH_RMII_RX_D0/ETH_MII_RX_D0/ADC12_IN14_33") (pintype "bidirectional"))
    )
    (net (code "86") (name "unconnected-(U8-PC5{slash}ETH_RMII_RX_D1{slash}ETH_MII_RX_D1{slash}ADC12_IN15-Pad34)") (class "Default")
      (node (ref "U8") (pin "34") (pinfunction "PC5/ETH_RMII_RX_D1/ETH_MII_RX_D1/ADC12_IN15_34") (pintype "bidirectional"))
    )
    (net (code "87") (name "unconnected-(U8-PC13{slash}RTC_AF1-Pad7)") (class "Default")
      (node (ref "U8") (pin "7") (pinfunction "PC13/RTC_AF1_7") (pintype "bidirectional"))
    )
    (net (code "88") (name "unconnected-(U8-PC14{slash}OSC32_IN-Pad8)") (class "Default")
      (node (ref "U8") (pin "8") (pinfunction "PC14/OSC32_IN_8") (pintype "bidirectional"))
    )
    (net (code "89") (name "unconnected-(U8-PC15{slash}OSC32_OUT-Pad9)") (class "Default")
      (node (ref "U8") (pin "9") (pinfunction "PC15/OSC32_OUT_9") (pintype "bidirectional"))
    )
    (net (code "90") (name "unconnected-(U8-PD0{slash}FSMC_D2{slash}CAN1_RX-Pad81)") (class "Default")
      (node (ref "U8") (pin "81") (pinfunction "PD0/FSMC_D2/CAN1_RX_81") (pintype "bidirectional"))
    )
    (net (code "91") (name "unconnected-(U8-PD1FSMC_D3{slash}CAN1_TX-Pad82)") (class "Default")
      (node (ref "U8") (pin "82") (pinfunction "PD1FSMC_D3/CAN1_TX_82") (pintype "bidirectional"))
    )
    (net (code "92") (name "unconnected-(U8-PD4{slash}FSMC_NOE{slash}USART2_RTS-Pad85)") (class "Default")
      (node (ref "U8") (pin "85") (pinfunction "PD4/FSMC_NOE/USART2_RTS_85") (pintype "bidirectional"))
    )
    (net (code "93") (name "unconnected-(U8-PD5{slash}FSMC_NWE{slash}USART2_TX-Pad86)") (class "Default")
      (node (ref "U8") (pin "86") (pinfunction "PD5/FSMC_NWE/USART2_TX_86") (pintype "bidirectional"))
    )
    (net (code "94") (name "unconnected-(U8-PD6{slash}FSMC_NWAIT{slash}USART2_RX-Pad87)") (class "Default")
      (node (ref "U8") (pin "87") (pinfunction "PD6/FSMC_NWAIT/USART2_RX_87") (pintype "bidirectional"))
    )
    (net (code "95") (name "unconnected-(U8-PD7{slash}USART2_CK{slash}FSMC_NE1{slash}FSMC_NCE2-Pad88)") (class "Default")
      (node (ref "U8") (pin "88") (pinfunction "PD7/USART2_CK/FSMC_NE1/FSMC_NCE2_88") (pintype "bidirectional"))
    )
    (net (code "96") (name "unconnected-(U8-PD10{slash}FSMC_D15{slash}USART3_CK-Pad57)") (class "Default")
      (node (ref "U8") (pin "57") (pinfunction "PD10/FSMC_D15/USART3_CK_57") (pintype "bidirectional"))
    )
    (net (code "97") (name "unconnected-(U8-PD11{slash}FSMC_A16{slash}USART3_CTS-Pad58)") (class "Default")
      (node (ref "U8") (pin "58") (pinfunction "PD11/FSMC_A16/USART3_CTS_58") (pintype "bidirectional"))
    )
    (net (code "98") (name "unconnected-(U8-PD14{slash}FSMC_D0{slash}TIM4_CH3-Pad61)") (class "Default")
      (node (ref "U8") (pin "61") (pinfunction "PD14/FSMC_D0/TIM4_CH3_61") (pintype "bidirectional"))
    )
    (net (code "99") (name "unconnected-(U8-PD15{slash}FSMC_D1{slash}TIM4_CH4-Pad62)") (class "Default")
      (node (ref "U8") (pin "62") (pinfunction "PD15/FSMC_D1/TIM4_CH4_62") (pintype "bidirectional"))
    )
    (net (code "100") (name "unconnected-(U8-PE3{slash}TRACED0{slash}FSMC_A19-Pad2)") (class "Default")
      (node (ref "U8") (pin "2") (pinfunction "PE3/TRACED0/FSMC_A19_2") (pintype "bidirectional"))
    )
    (net (code "101") (name "unconnected-(U8-PE7{slash}FSMC_D4{slash}TIM1_ETR-Pad38)") (class "Default")
      (node (ref "U8") (pin "38") (pinfunction "PE7/FSMC_D4/TIM1_ETR_38") (pintype "bidirectional"))
    )
    (net (code "102") (name "unconnected-(U8-PE8{slash}FSMC_D5{slash}TIM1_CH1N-Pad39)") (class "Default")
      (node (ref "U8") (pin "39") (pinfunction "PE8/FSMC_D5/TIM1_CH1N_39") (pintype "bidirectional"))
    )
    (net (code "103") (name "unconnected-(U8-PE9{slash}FSMC_D6{slash}TIM1_CH1-Pad40)") (class "Default")
      (node (ref "U8") (pin "40") (pinfunction "PE9/FSMC_D6/TIM1_CH1_40") (pintype "bidirectional"))
    )
    (net (code "104") (name "unconnected-(U8-PE10{slash}FSMC_D7{slash}TIM1_CH2N-Pad41)") (class "Default")
      (node (ref "U8") (pin "41") (pinfunction "PE10/FSMC_D7/TIM1_CH2N_41") (pintype "bidirectional"))
    )
    (net (code "105") (name "unconnected-(U8-PE11{slash}FSMC_D8{slash}TIM1_CH2-Pad42)") (class "Default")
      (node (ref "U8") (pin "42") (pinfunction "PE11/FSMC_D8/TIM1_CH2_42") (pintype "bidirectional"))
    )
    (net (code "106") (name "unconnected-(U8-PE12{slash}FSMC_D9{slash}TIM1_CH3N-Pad43)") (class "Default")
      (node (ref "U8") (pin "43") (pinfunction "PE12/FSMC_D9/TIM1_CH3N_43") (pintype "bidirectional"))
    )
    (net (code "107") (name "unconnected-(U8-PE13{slash}FSMC_D10{slash}TIM1_CH3-Pad44)") (class "Default")
      (node (ref "U8") (pin "44") (pinfunction "PE13/FSMC_D10/TIM1_CH3_44") (pintype "bidirectional"))
    )
    (net (code "108") (name "unconnected-(U8-PE14{slash}FSMC_D11{slash}TIM1_CH4-Pad45)") (class "Default")
      (node (ref "U8") (pin "45") (pinfunction "PE14/FSMC_D11/TIM1_CH4_45") (pintype "bidirectional"))
    )
    (net (code "109") (name "unconnected-(U8-PE15FSMC_D12{slash}TIM1_BKIN-Pad46)") (class "Default")
      (node (ref "U8") (pin "46") (pinfunction "PE15FSMC_D12/TIM1_BKIN_46") (pintype "bidirectional"))
    )
  )
)
